# PlayerTop.net
KiCad netlist of a schematic drawn in EAGLE
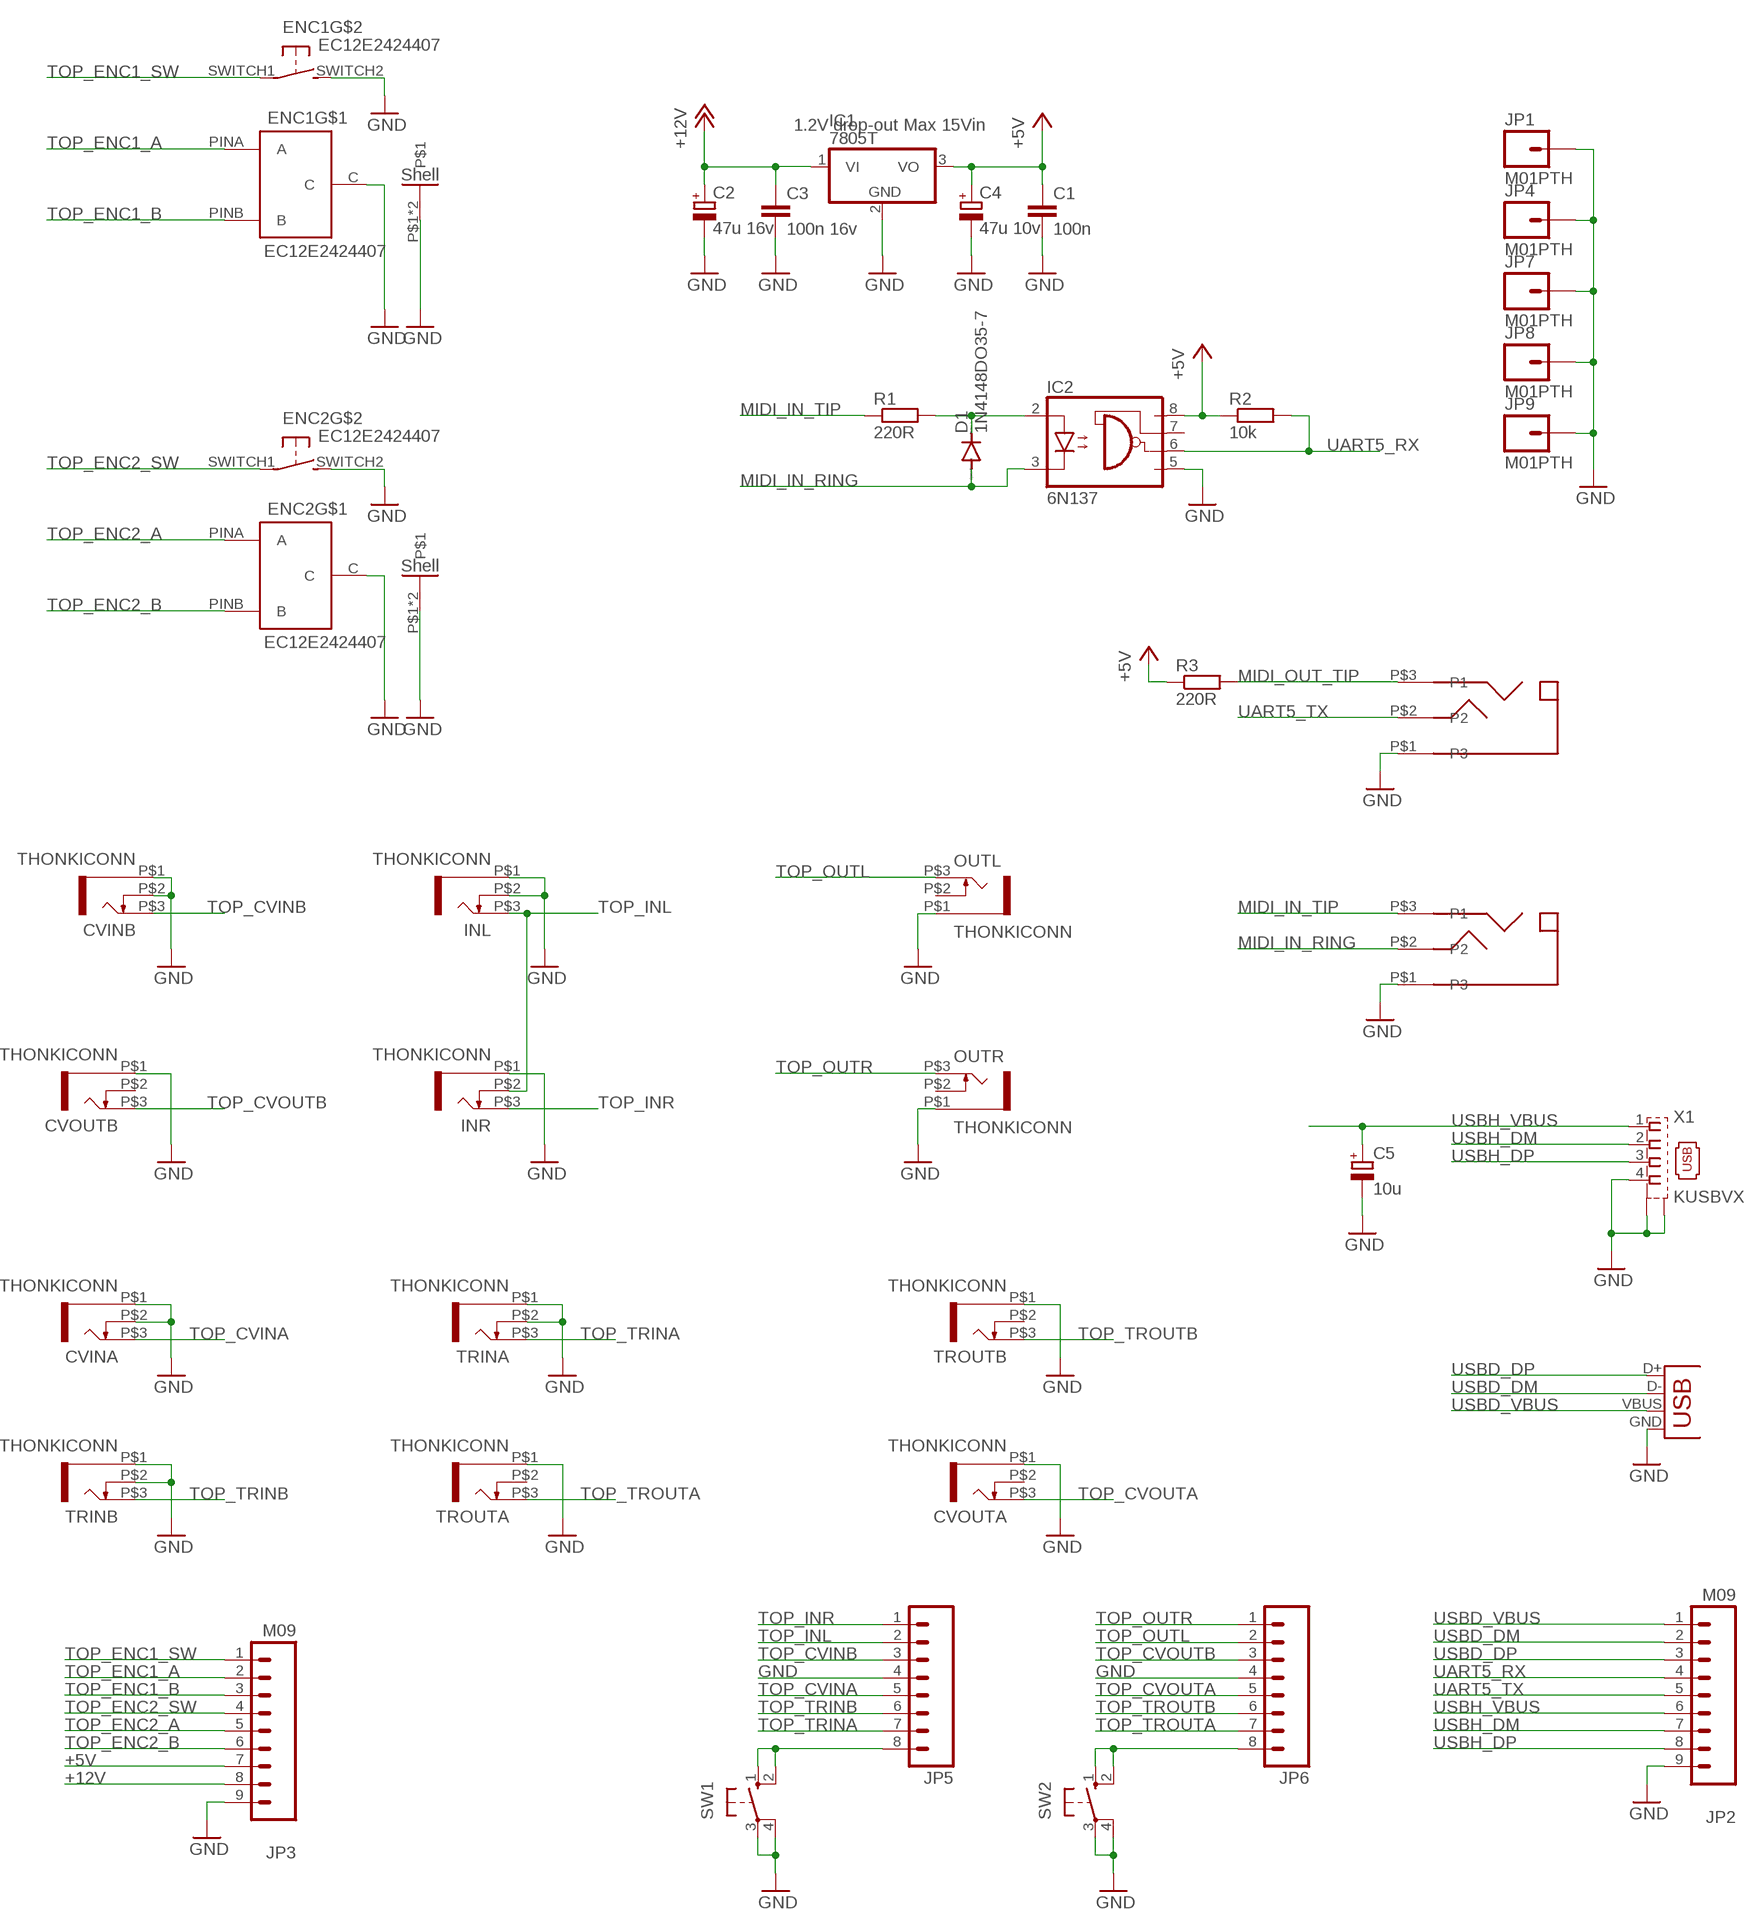
[diagram p0: schematic, sheet 1]

(export (version "E")
  (design (tool "Eeschema 10.0.6"))
  (components
    (comp (ref "C1")
      (value "100n")
      (footprint "eagle-import:C050-024X044")
      (libsource (lib "eagle-import") (part "C-EU050-024X044"))
    )
    (comp (ref "C2")
      (value "47u 16v")
      (footprint "eagle-import:E5-6")
      (libsource (lib "eagle-import") (part "CPOL-EUE5-6"))
    )
    (comp (ref "C3")
      (value "100n 16v")
      (footprint "eagle-import:C050-024X044")
      (libsource (lib "eagle-import") (part "C-EU050-024X044"))
    )
    (comp (ref "C4")
      (value "47u 10v")
      (footprint "eagle-import:E5-6")
      (libsource (lib "eagle-import") (part "CPOL-EUE5-6"))
    )
    (comp (ref "C5")
      (value "10u")
      (footprint "eagle-import:E2,5-6")
      (libsource (lib "eagle-import") (part "Rebel_15457297_CPOL-EUE2.5-6"))
    )
    (comp (ref "CVINA")
      (value "THONKICONN")
      (footprint "eagle-import:THONKICONN")
      (libsource (lib "eagle-import") (part "THONKICONN"))
    )
    (comp (ref "CVINB")
      (value "THONKICONN")
      (footprint "eagle-import:THONKICONN")
      (libsource (lib "eagle-import") (part "THONKICONN"))
    )
    (comp (ref "CVOUTA")
      (value "THONKICONN")
      (footprint "eagle-import:THONKICONN")
      (libsource (lib "eagle-import") (part "THONKICONN"))
    )
    (comp (ref "CVOUTB")
      (value "THONKICONN")
      (footprint "eagle-import:THONKICONN")
      (libsource (lib "eagle-import") (part "THONKICONN"))
    )
    (comp (ref "D1")
      (value "1N4148DO35-7")
      (footprint "eagle-import:DO35-7")
      (libsource (lib "eagle-import") (part "1N4148DO35-7"))
    )
    (comp (ref "ENC1")
      (value "EC12E2424407")
      (footprint "eagle-import:EC12E2424407")
      (libsource (lib "eagle-import") (part "EC12E2424407"))
    )
    (comp (ref "ENC2")
      (value "EC12E2424407")
      (footprint "eagle-import:EC12E2424407")
      (libsource (lib "eagle-import") (part "EC12E2424407"))
    )
    (comp (ref "IC1")
      (value "7805T")
      (footprint "eagle-import:TO220H")
      (libsource (lib "eagle-import") (part "78T05"))
    )
    (comp (ref "IC2")
      (value "6N137")
      (footprint "eagle-import:DIL08")
      (libsource (lib "eagle-import") (part "6N137"))
    )
    (comp (ref "INL")
      (value "THONKICONN")
      (footprint "eagle-import:THONKICONN")
      (libsource (lib "eagle-import") (part "THONKICONN"))
    )
    (comp (ref "INR")
      (value "THONKICONN")
      (footprint "eagle-import:THONKICONN")
      (libsource (lib "eagle-import") (part "THONKICONN"))
    )
    (comp (ref "JP1")
      (value "M01PTH")
      (footprint "eagle-import:1X01")
      (libsource (lib "eagle-import") (part "M01PTH"))
    )
    (comp (ref "JP2")
      (value "M09")
      (footprint "eagle-import:1X09")
      (libsource (lib "eagle-import") (part "M09"))
    )
    (comp (ref "JP3")
      (value "M09")
      (footprint "eagle-import:1X09")
      (libsource (lib "eagle-import") (part "M09"))
    )
    (comp (ref "JP4")
      (value "M01PTH")
      (footprint "eagle-import:1X01")
      (libsource (lib "eagle-import") (part "M01PTH"))
    )
    (comp (ref "JP5")
      (value "M081X08")
      (footprint "eagle-import:1X08")
      (libsource (lib "eagle-import") (part "M081X08"))
    )
    (comp (ref "JP6")
      (value "M081X08")
      (footprint "eagle-import:1X08")
      (libsource (lib "eagle-import") (part "M081X08"))
    )
    (comp (ref "JP7")
      (value "M01PTH")
      (footprint "eagle-import:1X01")
      (libsource (lib "eagle-import") (part "M01PTH"))
    )
    (comp (ref "JP8")
      (value "M01PTH")
      (footprint "eagle-import:1X01")
      (libsource (lib "eagle-import") (part "M01PTH"))
    )
    (comp (ref "JP9")
      (value "M01PTH")
      (footprint "eagle-import:1X01")
      (libsource (lib "eagle-import") (part "M01PTH"))
    )
    (comp (ref "MIDI_IN")
      (value "THONKICONN_STEREO")
      (footprint "eagle-import:THONKICONN_STEREO")
      (libsource (lib "eagle-import") (part "THONKICONN_STEREO"))
    )
    (comp (ref "MIDI_OUT")
      (value "THONKICONN_STEREO")
      (footprint "eagle-import:THONKICONN_STEREO")
      (libsource (lib "eagle-import") (part "THONKICONN_STEREO"))
    )
    (comp (ref "OUTL")
      (value "THONKICONN")
      (footprint "eagle-import:THONKICONN")
      (libsource (lib "eagle-import") (part "THONKICONN"))
    )
    (comp (ref "OUTR")
      (value "THONKICONN")
      (footprint "eagle-import:THONKICONN")
      (libsource (lib "eagle-import") (part "THONKICONN"))
    )
    (comp (ref "R1")
      (value "220R")
      (footprint "eagle-import:0204_7")
      (libsource (lib "eagle-import") (part "R-EU_0204/7"))
    )
    (comp (ref "R2")
      (value "10k")
      (footprint "eagle-import:0204_7")
      (libsource (lib "eagle-import") (part "R-EU_0204/7"))
    )
    (comp (ref "R3")
      (value "220R")
      (footprint "eagle-import:0204_7")
      (libsource (lib "eagle-import") (part "R-EU_0204/7"))
    )
    (comp (ref "SW1")
      (value "10-XX")
      (footprint "eagle-import:B3F-10XX")
      (fields (field (name "MPN") "B3F-1000"))
      (libsource (lib "eagle-import") (part "10-XX"))
    )
    (comp (ref "SW2")
      (value "10-XX")
      (footprint "eagle-import:B3F-10XX")
      (fields (field (name "MPN") "B3F-1000"))
      (libsource (lib "eagle-import") (part "10-XX"))
    )
    (comp (ref "TRINA")
      (value "THONKICONN")
      (footprint "eagle-import:THONKICONN")
      (libsource (lib "eagle-import") (part "THONKICONN"))
    )
    (comp (ref "TRINB")
      (value "THONKICONN")
      (footprint "eagle-import:THONKICONN")
      (libsource (lib "eagle-import") (part "THONKICONN"))
    )
    (comp (ref "TROUTA")
      (value "THONKICONN")
      (footprint "eagle-import:THONKICONN")
      (libsource (lib "eagle-import") (part "THONKICONN"))
    )
    (comp (ref "TROUTB")
      (value "THONKICONN")
      (footprint "eagle-import:THONKICONN")
      (libsource (lib "eagle-import") (part "THONKICONN"))
    )
    (comp (ref "X1")
      (value "KUSBVX")
      (footprint "eagle-import:KUSBVX")
      (libsource (lib "eagle-import") (part "KUSBVX"))
    )
    (comp (ref "X2")
      (value "USBPTH-VERTICAL")
      (footprint "eagle-import:USB-B-PTH-VERTICAL")
      (libsource (lib "eagle-import") (part "USBPTH-VERTICAL"))
    )
  )
  (nets
    (net (code "1") (name "+5V") (class "Default")
      (node (ref "C1") (pin "1") (pinfunction "1_1") (pintype "passive"))
      (node (ref "C4") (pin "+") (pinfunction "+_+") (pintype "passive"))
      (node (ref "IC1") (pin "3") (pinfunction "VO_3") (pintype "passive"))
      (node (ref "IC2") (pin "8") (pinfunction "VCC_8") (pintype "passive"))
      (node (ref "JP3") (pin "7") (pinfunction "7_7") (pintype "passive"))
      (node (ref "R2") (pin "1") (pinfunction "1_1") (pintype "passive"))
      (node (ref "R3") (pin "1") (pinfunction "1_1") (pintype "passive"))
    )
    (net (code "2") (name "+12V") (class "Default")
      (node (ref "C2") (pin "+") (pinfunction "+_+") (pintype "passive"))
      (node (ref "C3") (pin "1") (pinfunction "1_1") (pintype "passive"))
      (node (ref "IC1") (pin "1") (pinfunction "VI_1") (pintype "input"))
      (node (ref "JP3") (pin "8") (pinfunction "8_8") (pintype "passive"))
    )
    (net (code "3") (name "/MIDI_IN_RING") (class "Default")
      (node (ref "D1") (pin "A") (pinfunction "A_A") (pintype "passive"))
      (node (ref "IC2") (pin "3") (pinfunction "C_3") (pintype "passive"))
      (node (ref "MIDI_IN") (pin "P$2") (pinfunction "P2_P$2") (pintype "bidirectional"))
    )
    (net (code "4") (name "/MIDI_IN_TIP") (class "Default")
      (node (ref "MIDI_IN") (pin "P$3") (pinfunction "P1_P$3") (pintype "bidirectional"))
      (node (ref "R1") (pin "1") (pinfunction "1_1") (pintype "passive"))
    )
    (net (code "5") (name "/MIDI_OUT_TIP") (class "Default")
      (node (ref "MIDI_OUT") (pin "P$3") (pinfunction "P1_P$3") (pintype "bidirectional"))
      (node (ref "R3") (pin "2") (pinfunction "2_2") (pintype "passive"))
    )
    (net (code "6") (name "/TOP_CVINA") (class "Default")
      (node (ref "CVINA") (pin "P$3") (pinfunction "3_P$3") (pintype "passive"))
      (node (ref "JP5") (pin "5") (pinfunction "5_5") (pintype "passive"))
    )
    (net (code "7") (name "/TOP_CVINB") (class "Default")
      (node (ref "CVINB") (pin "P$3") (pinfunction "3_P$3") (pintype "passive"))
      (node (ref "JP5") (pin "3") (pinfunction "3_3") (pintype "passive"))
    )
    (net (code "8") (name "/TOP_CVOUTA") (class "Default")
      (node (ref "CVOUTA") (pin "P$3") (pinfunction "3_P$3") (pintype "passive"))
      (node (ref "JP6") (pin "5") (pinfunction "5_5") (pintype "passive"))
    )
    (net (code "9") (name "/TOP_CVOUTB") (class "Default")
      (node (ref "CVOUTB") (pin "P$3") (pinfunction "3_P$3") (pintype "passive"))
      (node (ref "JP6") (pin "3") (pinfunction "3_3") (pintype "passive"))
    )
    (net (code "10") (name "/TOP_ENC1_A") (class "Default")
      (node (ref "ENC1") (pin "PINA") (pinfunction "A_PINA") (pintype "bidirectional"))
      (node (ref "JP3") (pin "2") (pinfunction "2_2") (pintype "passive"))
    )
    (net (code "11") (name "/TOP_ENC1_B") (class "Default")
      (node (ref "ENC1") (pin "PINB") (pinfunction "B_PINB") (pintype "bidirectional"))
      (node (ref "JP3") (pin "3") (pinfunction "3_3") (pintype "passive"))
    )
    (net (code "12") (name "/TOP_ENC1_SW") (class "Default")
      (node (ref "ENC1") (pin "SWITCH1") (pinfunction "P_SWITCH1") (pintype "passive"))
      (node (ref "JP3") (pin "1") (pinfunction "1_1") (pintype "passive"))
    )
    (net (code "13") (name "/TOP_ENC2_A") (class "Default")
      (node (ref "ENC2") (pin "PINA") (pinfunction "A_PINA") (pintype "bidirectional"))
      (node (ref "JP3") (pin "5") (pinfunction "5_5") (pintype "passive"))
    )
    (net (code "14") (name "/TOP_ENC2_B") (class "Default")
      (node (ref "ENC2") (pin "PINB") (pinfunction "B_PINB") (pintype "bidirectional"))
      (node (ref "JP3") (pin "6") (pinfunction "6_6") (pintype "passive"))
    )
    (net (code "15") (name "/TOP_ENC2_SW") (class "Default")
      (node (ref "ENC2") (pin "SWITCH1") (pinfunction "P_SWITCH1") (pintype "passive"))
      (node (ref "JP3") (pin "4") (pinfunction "4_4") (pintype "passive"))
    )
    (net (code "16") (name "/TOP_INL") (class "Default")
      (node (ref "INL") (pin "P$3") (pinfunction "3_P$3") (pintype "passive"))
      (node (ref "INR") (pin "P$2") (pinfunction "4_P$2") (pintype "passive"))
      (node (ref "JP5") (pin "2") (pinfunction "2_2") (pintype "passive"))
    )
    (net (code "17") (name "/TOP_INR") (class "Default")
      (node (ref "INR") (pin "P$3") (pinfunction "3_P$3") (pintype "passive"))
      (node (ref "JP5") (pin "1") (pinfunction "1_1") (pintype "passive"))
    )
    (net (code "18") (name "/TOP_OUTL") (class "Default")
      (node (ref "JP6") (pin "2") (pinfunction "2_2") (pintype "passive"))
      (node (ref "OUTL") (pin "P$3") (pinfunction "3_P$3") (pintype "passive"))
    )
    (net (code "19") (name "/TOP_OUTR") (class "Default")
      (node (ref "JP6") (pin "1") (pinfunction "1_1") (pintype "passive"))
      (node (ref "OUTR") (pin "P$3") (pinfunction "3_P$3") (pintype "passive"))
    )
    (net (code "20") (name "/TOP_TRINA") (class "Default")
      (node (ref "JP5") (pin "7") (pinfunction "7_7") (pintype "passive"))
      (node (ref "TRINA") (pin "P$3") (pinfunction "3_P$3") (pintype "passive"))
    )
    (net (code "21") (name "/TOP_TRINB") (class "Default")
      (node (ref "JP5") (pin "6") (pinfunction "6_6") (pintype "passive"))
      (node (ref "TRINB") (pin "P$3") (pinfunction "3_P$3") (pintype "passive"))
    )
    (net (code "22") (name "/TOP_TROUTA") (class "Default")
      (node (ref "JP6") (pin "7") (pinfunction "7_7") (pintype "passive"))
      (node (ref "TROUTA") (pin "P$3") (pinfunction "3_P$3") (pintype "passive"))
    )
    (net (code "23") (name "/TOP_TROUTB") (class "Default")
      (node (ref "JP6") (pin "6") (pinfunction "6_6") (pintype "passive"))
      (node (ref "TROUTB") (pin "P$3") (pinfunction "3_P$3") (pintype "passive"))
    )
    (net (code "24") (name "/UART5_RX") (class "Default")
      (node (ref "IC2") (pin "6") (pinfunction "VO_6") (pintype "passive"))
      (node (ref "JP2") (pin "4") (pinfunction "4_4") (pintype "passive"))
      (node (ref "R2") (pin "2") (pinfunction "2_2") (pintype "passive"))
    )
    (net (code "25") (name "/UART5_TX") (class "Default")
      (node (ref "JP2") (pin "5") (pinfunction "5_5") (pintype "passive"))
      (node (ref "MIDI_OUT") (pin "P$2") (pinfunction "P2_P$2") (pintype "bidirectional"))
    )
    (net (code "26") (name "/USBD_DM") (class "Default")
      (node (ref "JP2") (pin "2") (pinfunction "2_2") (pintype "passive"))
      (node (ref "X2") (pin "D-") (pinfunction "D-_D-") (pintype "bidirectional"))
    )
    (net (code "27") (name "/USBD_DP") (class "Default")
      (node (ref "JP2") (pin "3") (pinfunction "3_3") (pintype "passive"))
      (node (ref "X2") (pin "D+") (pinfunction "D+_D+") (pintype "bidirectional"))
    )
    (net (code "28") (name "/USBD_VBUS") (class "Default")
      (node (ref "JP2") (pin "1") (pinfunction "1_1") (pintype "passive"))
      (node (ref "X2") (pin "VBUS") (pinfunction "VBUS_VBUS") (pintype "bidirectional"))
    )
    (net (code "29") (name "/USBH_DM") (class "Default")
      (node (ref "JP2") (pin "7") (pinfunction "7_7") (pintype "passive"))
      (node (ref "X1") (pin "2") (pinfunction "2_2") (pintype "passive"))
    )
    (net (code "30") (name "/USBH_DP") (class "Default")
      (node (ref "JP2") (pin "8") (pinfunction "8_8") (pintype "passive"))
      (node (ref "X1") (pin "3") (pinfunction "3_3") (pintype "passive"))
    )
    (net (code "31") (name "/USBH_VBUS") (class "Default")
      (node (ref "C5") (pin "+") (pinfunction "+_+") (pintype "passive"))
      (node (ref "JP2") (pin "6") (pinfunction "6_6") (pintype "passive"))
      (node (ref "X1") (pin "1") (pinfunction "1_1") (pintype "passive"))
    )
    (net (code "32") (name "GND") (class "Default")
      (node (ref "C1") (pin "2") (pinfunction "2_2") (pintype "passive"))
      (node (ref "C2") (pin "-") (pinfunction "-_-") (pintype "passive"))
      (node (ref "C3") (pin "2") (pinfunction "2_2") (pintype "passive"))
      (node (ref "C4") (pin "-") (pinfunction "-_-") (pintype "passive"))
      (node (ref "C5") (pin "-") (pinfunction "-_-") (pintype "passive"))
      (node (ref "CVINA") (pin "P$1") (pinfunction "5_P$1") (pintype "passive"))
      (node (ref "CVINA") (pin "P$2") (pinfunction "4_P$2") (pintype "passive"))
      (node (ref "CVINB") (pin "P$1") (pinfunction "5_P$1") (pintype "passive"))
      (node (ref "CVINB") (pin "P$2") (pinfunction "4_P$2") (pintype "passive"))
      (node (ref "CVOUTA") (pin "P$1") (pinfunction "5_P$1") (pintype "passive"))
      (node (ref "CVOUTB") (pin "P$1") (pinfunction "5_P$1") (pintype "passive"))
      (node (ref "ENC1") (pin "C") (pinfunction "C_C") (pintype "bidirectional"))
      (node (ref "ENC1") (pin "P$1") (pinfunction "P$1_P$1") (pintype "bidirectional"))
      (node (ref "ENC1") (pin "P$2") (pinfunction "P$1_P$2") (pintype "bidirectional"))
      (node (ref "ENC1") (pin "SWITCH2") (pinfunction "S_SWITCH2") (pintype "passive"))
      (node (ref "ENC2") (pin "C") (pinfunction "C_C") (pintype "bidirectional"))
      (node (ref "ENC2") (pin "P$1") (pinfunction "P$1_P$1") (pintype "bidirectional"))
      (node (ref "ENC2") (pin "P$2") (pinfunction "P$1_P$2") (pintype "bidirectional"))
      (node (ref "ENC2") (pin "SWITCH2") (pinfunction "S_SWITCH2") (pintype "passive"))
      (node (ref "IC1") (pin "2") (pinfunction "GND_2") (pintype "passive"))
      (node (ref "IC2") (pin "5") (pinfunction "GND_5") (pintype "passive"))
      (node (ref "INL") (pin "P$1") (pinfunction "5_P$1") (pintype "passive"))
      (node (ref "INL") (pin "P$2") (pinfunction "4_P$2") (pintype "passive"))
      (node (ref "INR") (pin "P$1") (pinfunction "5_P$1") (pintype "passive"))
      (node (ref "JP1") (pin "1") (pinfunction "1_1") (pintype "passive"))
      (node (ref "JP2") (pin "9") (pinfunction "9_9") (pintype "passive"))
      (node (ref "JP3") (pin "9") (pinfunction "9_9") (pintype "passive"))
      (node (ref "JP4") (pin "1") (pinfunction "1_1") (pintype "passive"))
      (node (ref "JP5") (pin "4") (pinfunction "4_4") (pintype "passive"))
      (node (ref "JP6") (pin "4") (pinfunction "4_4") (pintype "passive"))
      (node (ref "JP7") (pin "1") (pinfunction "1_1") (pintype "passive"))
      (node (ref "JP8") (pin "1") (pinfunction "1_1") (pintype "passive"))
      (node (ref "JP9") (pin "1") (pinfunction "1_1") (pintype "passive"))
      (node (ref "MIDI_IN") (pin "P$1") (pinfunction "P3_P$1") (pintype "bidirectional"))
      (node (ref "MIDI_OUT") (pin "P$1") (pinfunction "P3_P$1") (pintype "bidirectional"))
      (node (ref "OUTL") (pin "P$1") (pinfunction "5_P$1") (pintype "passive"))
      (node (ref "OUTR") (pin "P$1") (pinfunction "5_P$1") (pintype "passive"))
      (node (ref "SW1") (pin "3") (pinfunction "P_3") (pintype "passive"))
      (node (ref "SW1") (pin "4") (pinfunction "P1_4") (pintype "passive"))
      (node (ref "SW2") (pin "3") (pinfunction "P_3") (pintype "passive"))
      (node (ref "SW2") (pin "4") (pinfunction "P1_4") (pintype "passive"))
      (node (ref "TRINA") (pin "P$1") (pinfunction "5_P$1") (pintype "passive"))
      (node (ref "TRINA") (pin "P$2") (pinfunction "4_P$2") (pintype "passive"))
      (node (ref "TRINB") (pin "P$1") (pinfunction "5_P$1") (pintype "passive"))
      (node (ref "TRINB") (pin "P$2") (pinfunction "4_P$2") (pintype "passive"))
      (node (ref "TROUTA") (pin "P$1") (pinfunction "5_P$1") (pintype "passive"))
      (node (ref "TROUTB") (pin "P$1") (pinfunction "5_P$1") (pintype "passive"))
      (node (ref "X1") (pin "4") (pinfunction "4_4") (pintype "passive"))
      (node (ref "X1") (pin "M1") (pinfunction "S1_M1") (pintype "passive"))
      (node (ref "X1") (pin "M2") (pinfunction "S2_M2") (pintype "passive"))
      (node (ref "X2") (pin "GND") (pinfunction "GND_GND") (pintype "bidirectional"))
    )
    (net (code "33") (name "Net-(IC2-A)") (class "Default")
      (node (ref "D1") (pin "C") (pinfunction "C_C") (pintype "passive"))
      (node (ref "IC2") (pin "2") (pinfunction "A_2") (pintype "passive"))
      (node (ref "R1") (pin "2") (pinfunction "2_2") (pintype "passive"))
    )
    (net (code "34") (name "Net-(SW1-S)") (class "Default")
      (node (ref "JP5") (pin "8") (pinfunction "8_8") (pintype "passive"))
      (node (ref "SW1") (pin "1") (pinfunction "S_1") (pintype "passive"))
      (node (ref "SW1") (pin "2") (pinfunction "S1_2") (pintype "passive"))
    )
    (net (code "35") (name "Net-(SW2-S)") (class "Default")
      (node (ref "JP6") (pin "8") (pinfunction "8_8") (pintype "passive"))
      (node (ref "SW2") (pin "1") (pinfunction "S_1") (pintype "passive"))
      (node (ref "SW2") (pin "2") (pinfunction "S1_2") (pintype "passive"))
    )
    (net (code "36") (name "unconnected-(CVOUTA-4-PadP$2)") (class "Default")
      (node (ref "CVOUTA") (pin "P$2") (pinfunction "4_P$2") (pintype "passive"))
    )
    (net (code "37") (name "unconnected-(CVOUTB-4-PadP$2)") (class "Default")
      (node (ref "CVOUTB") (pin "P$2") (pinfunction "4_P$2") (pintype "passive"))
    )
    (net (code "38") (name "unconnected-(IC2-VE-Pad7)") (class "Default")
      (node (ref "IC2") (pin "7") (pinfunction "VE_7") (pintype "passive"))
    )
    (net (code "39") (name "unconnected-(OUTL-4-PadP$2)") (class "Default")
      (node (ref "OUTL") (pin "P$2") (pinfunction "4_P$2") (pintype "passive"))
    )
    (net (code "40") (name "unconnected-(OUTR-4-PadP$2)") (class "Default")
      (node (ref "OUTR") (pin "P$2") (pinfunction "4_P$2") (pintype "passive"))
    )
    (net (code "41") (name "unconnected-(TROUTA-4-PadP$2)") (class "Default")
      (node (ref "TROUTA") (pin "P$2") (pinfunction "4_P$2") (pintype "passive"))
    )
    (net (code "42") (name "unconnected-(TROUTB-4-PadP$2)") (class "Default")
      (node (ref "TROUTB") (pin "P$2") (pinfunction "4_P$2") (pintype "passive"))
    )
  )
)
